# Quadcopter.net
KiCad netlist of a schematic drawn in EAGLE
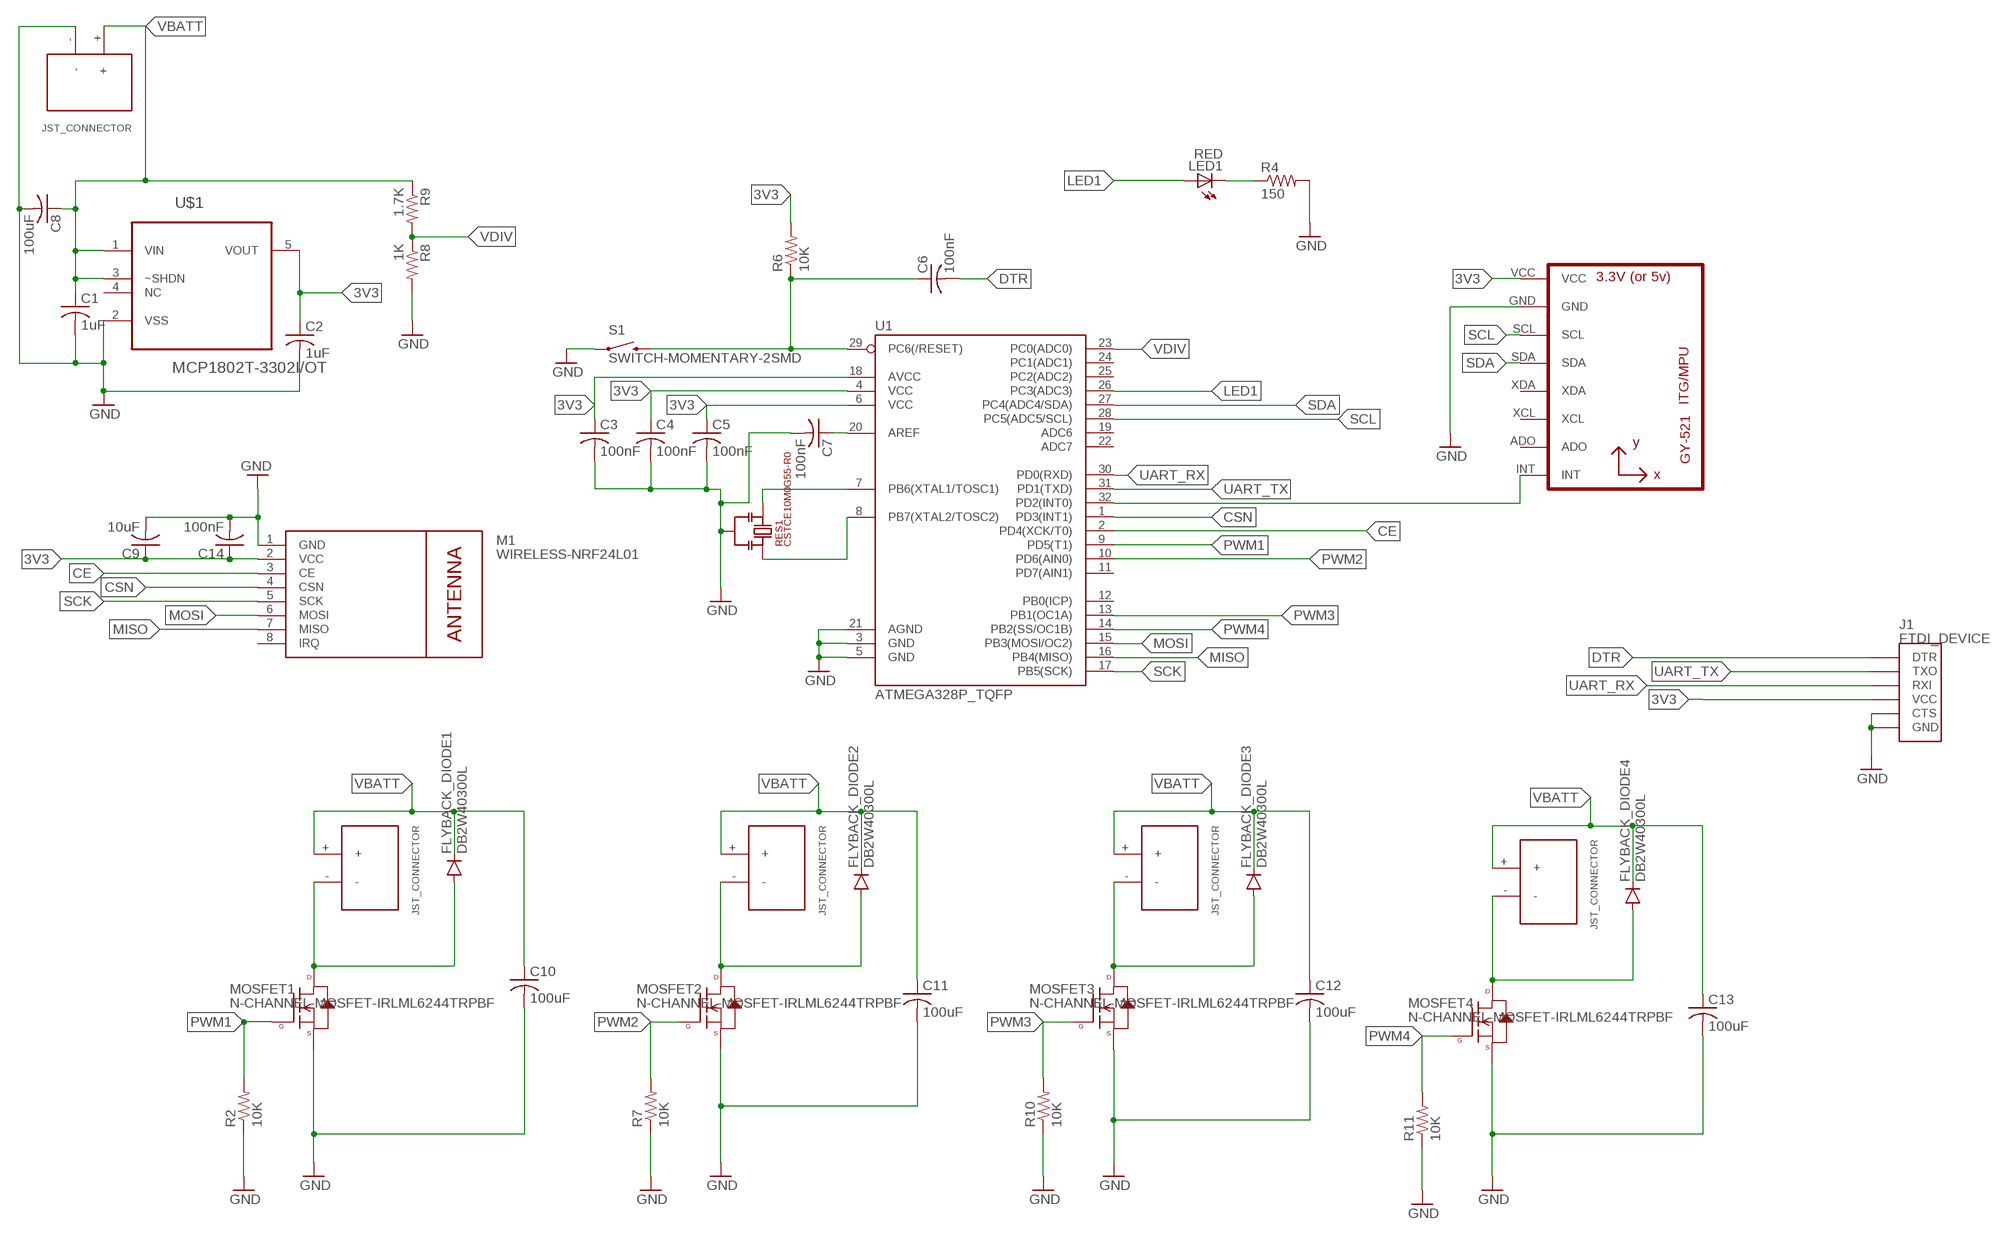
[diagram p0: schematic, sheet 1]

(export (version "E")
  (design (tool "Eeschema 10.0.6"))
  (components
    (comp (ref "C1")
      (value "1uF")
      (footprint "eagle-import:C0603")
      (libsource (lib "eagle-import") (part "C-USC0603"))
    )
    (comp (ref "C2")
      (value "1uF")
      (footprint "eagle-import:C0603")
      (libsource (lib "eagle-import") (part "C-USC0603"))
    )
    (comp (ref "C3")
      (value "100nF")
      (footprint "eagle-import:C0603")
      (libsource (lib "eagle-import") (part "C-USC0603"))
    )
    (comp (ref "C4")
      (value "100nF")
      (footprint "eagle-import:C0603")
      (libsource (lib "eagle-import") (part "C-USC0603"))
    )
    (comp (ref "C5")
      (value "100nF")
      (footprint "eagle-import:C0603")
      (libsource (lib "eagle-import") (part "C-USC0603"))
    )
    (comp (ref "C6")
      (value "100nF")
      (footprint "eagle-import:C0603")
      (libsource (lib "eagle-import") (part "C-USC0603"))
    )
    (comp (ref "C7")
      (value "100nF")
      (footprint "eagle-import:C0603")
      (libsource (lib "eagle-import") (part "C-USC0603"))
    )
    (comp (ref "C8")
      (value "100uF")
      (footprint "eagle-import:C1210")
      (libsource (lib "eagle-import") (part "C-USC1210"))
    )
    (comp (ref "C9")
      (value "10uF")
      (footprint "eagle-import:C0603")
      (libsource (lib "eagle-import") (part "C-USC0603"))
    )
    (comp (ref "C10")
      (value "100uF")
      (footprint "eagle-import:C1210")
      (libsource (lib "eagle-import") (part "C-USC1210"))
    )
    (comp (ref "C11")
      (value "100uF")
      (footprint "eagle-import:C1210")
      (libsource (lib "eagle-import") (part "C-USC1210"))
    )
    (comp (ref "C12")
      (value "100uF")
      (footprint "eagle-import:C1210")
      (libsource (lib "eagle-import") (part "C-USC1210"))
    )
    (comp (ref "C13")
      (value "100uF")
      (footprint "eagle-import:C1210")
      (libsource (lib "eagle-import") (part "C-USC1210"))
    )
    (comp (ref "C14")
      (value "100nF")
      (footprint "eagle-import:C0603")
      (libsource (lib "eagle-import") (part "C-USC0603"))
    )
    (comp (ref "FLYBACK_DIODE1")
      (value "DB2W40300L")
      (footprint "eagle-import:MINI2-F3-B")
      (libsource (lib "eagle-import") (part "DB2W40300L"))
    )
    (comp (ref "FLYBACK_DIODE2")
      (value "DB2W40300L")
      (footprint "eagle-import:MINI2-F3-B")
      (libsource (lib "eagle-import") (part "DB2W40300L"))
    )
    (comp (ref "FLYBACK_DIODE3")
      (value "DB2W40300L")
      (footprint "eagle-import:MINI2-F3-B")
      (libsource (lib "eagle-import") (part "DB2W40300L"))
    )
    (comp (ref "FLYBACK_DIODE4")
      (value "DB2W40300L")
      (footprint "eagle-import:MINI2-F3-B")
      (libsource (lib "eagle-import") (part "DB2W40300L"))
    )
    (comp (ref "J1")
      (value "FTDI_DEVICE")
      (footprint "eagle-import:FTDI_DEVICE_SIDE")
      (libsource (lib "eagle-import") (part "FTDI_DEVICE"))
    )
    (comp (ref "LED1")
      (value "RED")
      (footprint "eagle-import:CHIP-LED0603")
      (libsource (lib "eagle-import") (part "LEDCHIP-LED0603"))
    )
    (comp (ref "M1")
      (value "WIRELESS-NRF24L01")
      (footprint "eagle-import:WIRELESS-NRF24L01")
      (libsource (lib "eagle-import") (part "WIRELESS-NRF24L01"))
    )
    (comp (ref "MOSFET1")
      (value "N-CHANNEL-MOSFET-IRLML6244TRPBF")
      (footprint "eagle-import:SOT23-3")
      (libsource (lib "eagle-import") (part "N-CHANNEL-MOSFET-IRLML6244TRPBF"))
    )
    (comp (ref "MOSFET2")
      (value "N-CHANNEL-MOSFET-IRLML6244TRPBF")
      (footprint "eagle-import:SOT23-3")
      (libsource (lib "eagle-import") (part "N-CHANNEL-MOSFET-IRLML6244TRPBF"))
    )
    (comp (ref "MOSFET3")
      (value "N-CHANNEL-MOSFET-IRLML6244TRPBF")
      (footprint "eagle-import:SOT23-3")
      (libsource (lib "eagle-import") (part "N-CHANNEL-MOSFET-IRLML6244TRPBF"))
    )
    (comp (ref "MOSFET4")
      (value "N-CHANNEL-MOSFET-IRLML6244TRPBF")
      (footprint "eagle-import:SOT23-3")
      (libsource (lib "eagle-import") (part "N-CHANNEL-MOSFET-IRLML6244TRPBF"))
    )
    (comp (ref "MOTOR")
      (value "JST_CONNECTOR_FEMALE")
      (footprint "eagle-import:JST_CONNECTOR_FEMALE")
      (libsource (lib "eagle-import") (part "JST_CONNECTOR_FEMALE"))
    )
    (comp (ref "MOTOR1")
      (value "JST_CONNECTOR_FEMALE")
      (footprint "eagle-import:JST_CONNECTOR_FEMALE")
      (libsource (lib "eagle-import") (part "JST_CONNECTOR_FEMALE"))
    )
    (comp (ref "MOTOR2")
      (value "JST_CONNECTOR_FEMALE")
      (footprint "eagle-import:JST_CONNECTOR_FEMALE")
      (libsource (lib "eagle-import") (part "JST_CONNECTOR_FEMALE"))
    )
    (comp (ref "MOTOR3")
      (value "JST_CONNECTOR_FEMALE")
      (footprint "eagle-import:JST_CONNECTOR_FEMALE")
      (libsource (lib "eagle-import") (part "JST_CONNECTOR_FEMALE"))
    )
    (comp (ref "R2")
      (value "10K")
      (footprint "eagle-import:R0603")
      (libsource (lib "eagle-import") (part "R-US_R0603"))
    )
    (comp (ref "R4")
      (value "150")
      (footprint "eagle-import:R0603")
      (libsource (lib "eagle-import") (part "R-US_R0603"))
    )
    (comp (ref "R6")
      (value "10K")
      (footprint "eagle-import:R0603")
      (libsource (lib "eagle-import") (part "R-US_R0603"))
    )
    (comp (ref "R7")
      (value "10K")
      (footprint "eagle-import:R0603")
      (libsource (lib "eagle-import") (part "R-US_R0603"))
    )
    (comp (ref "R8")
      (value "1K")
      (footprint "eagle-import:R0603")
      (libsource (lib "eagle-import") (part "R-US_R0603"))
    )
    (comp (ref "R9")
      (value "1.7K")
      (footprint "eagle-import:R0603")
      (libsource (lib "eagle-import") (part "R-US_R0603"))
    )
    (comp (ref "R10")
      (value "10K")
      (footprint "eagle-import:R0603")
      (libsource (lib "eagle-import") (part "R-US_R0603"))
    )
    (comp (ref "R11")
      (value "10K")
      (footprint "eagle-import:R0603")
      (libsource (lib "eagle-import") (part "R-US_R0603"))
    )
    (comp (ref "RES1")
      (value "CSTCE10M0G55-R0")
      (footprint "eagle-import:CSTCE16M0V53-R0")
      (libsource (lib "eagle-import") (part "CSTCE-RESONATOR"))
    )
    (comp (ref "S1")
      (value "SWITCH-MOMENTARY-2SMD")
      (footprint "eagle-import:TACTILE-SWITCH-SMD")
      (libsource (lib "eagle-import") (part "SWITCH-MOMENTARY-2SMD"))
    )
    (comp (ref "U$1")
      (value "MCP1802T-3302I/OT")
      (footprint "eagle-import:SOT95P270X145-5N")
      (fields (field (name "MPN") "MCP1802T-3002I/OT"))
      (libsource (lib "eagle-import") (part "MCP1802T-3002I/OT"))
    )
    (comp (ref "U$2")
      (value "JST_Battery")
      (footprint "eagle-import:JST_CONNECTOR_FEMALE")
      (libsource (lib "eagle-import") (part "JST_CONNECTOR_FEMALE"))
    )
    (comp (ref "U1")
      (value "ATMEGA328P_TQFP")
      (footprint "eagle-import:TQFP32-08")
      (libsource (lib "eagle-import") (part "ATMEGA328P_TQFP"))
    )
    (comp (ref "U3")
      (value "GY-521MPU6050")
      (footprint "eagle-import:GY-521")
      (libsource (lib "eagle-import") (part "GY-521MPU6050"))
    )
  )
  (nets
    (net (code "1") (name "3V3") (class "Default")
      (node (ref "C14") (pin "1") (pinfunction "1_1") (pintype "passive"))
      (node (ref "C2") (pin "1") (pinfunction "1_1") (pintype "passive"))
      (node (ref "C3") (pin "1") (pinfunction "1_1") (pintype "passive"))
      (node (ref "C4") (pin "1") (pinfunction "1_1") (pintype "passive"))
      (node (ref "C5") (pin "1") (pinfunction "1_1") (pintype "passive"))
      (node (ref "C9") (pin "1") (pinfunction "1_1") (pintype "passive"))
      (node (ref "J1") (pin "P$4") (pinfunction "VCC_P$4") (pintype "bidirectional"))
      (node (ref "M1") (pin "2") (pinfunction "VCC_2") (pintype "power_in"))
      (node (ref "R6") (pin "2") (pinfunction "2_2") (pintype "passive"))
      (node (ref "U$1") (pin "5") (pinfunction "VOUT_5") (pintype "output"))
      (node (ref "U1") (pin "18") (pinfunction "AVCC_18") (pintype "bidirectional"))
      (node (ref "U1") (pin "4") (pinfunction "VCC_4") (pintype "bidirectional"))
      (node (ref "U1") (pin "6") (pinfunction "VCC_6") (pintype "bidirectional"))
      (node (ref "U3") (pin "VCC") (pinfunction "VCC_VCC") (pintype "bidirectional"))
    )
    (net (code "2") (name "CE") (class "Default")
      (node (ref "M1") (pin "3") (pinfunction "CE_3") (pintype "bidirectional"))
      (node (ref "U1") (pin "2") (pinfunction "PD4(XCK/T0)_2") (pintype "bidirectional"))
    )
    (net (code "3") (name "CSN") (class "Default")
      (node (ref "M1") (pin "4") (pinfunction "CSN_4") (pintype "bidirectional"))
      (node (ref "U1") (pin "1") (pinfunction "PD3(INT1)_1") (pintype "bidirectional"))
    )
    (net (code "4") (name "DTR") (class "Default")
      (node (ref "C6") (pin "2") (pinfunction "2_2") (pintype "passive"))
      (node (ref "J1") (pin "P$1") (pinfunction "DTR_P$1") (pintype "bidirectional"))
    )
    (net (code "5") (name "GND") (class "Default")
      (node (ref "C1") (pin "2") (pinfunction "2_2") (pintype "passive"))
      (node (ref "C10") (pin "2") (pinfunction "2_2") (pintype "passive"))
      (node (ref "C11") (pin "2") (pinfunction "2_2") (pintype "passive"))
      (node (ref "C12") (pin "2") (pinfunction "2_2") (pintype "passive"))
      (node (ref "C13") (pin "2") (pinfunction "2_2") (pintype "passive"))
      (node (ref "C14") (pin "2") (pinfunction "2_2") (pintype "passive"))
      (node (ref "C2") (pin "2") (pinfunction "2_2") (pintype "passive"))
      (node (ref "C3") (pin "2") (pinfunction "2_2") (pintype "passive"))
      (node (ref "C4") (pin "2") (pinfunction "2_2") (pintype "passive"))
      (node (ref "C5") (pin "2") (pinfunction "2_2") (pintype "passive"))
      (node (ref "C7") (pin "2") (pinfunction "2_2") (pintype "passive"))
      (node (ref "C8") (pin "2") (pinfunction "2_2") (pintype "passive"))
      (node (ref "C9") (pin "2") (pinfunction "2_2") (pintype "passive"))
      (node (ref "J1") (pin "P$5") (pinfunction "CTS_P$5") (pintype "bidirectional"))
      (node (ref "J1") (pin "P$6") (pinfunction "GND_P$6") (pintype "bidirectional"))
      (node (ref "M1") (pin "1") (pinfunction "GND_1") (pintype "power_in"))
      (node (ref "MOSFET1") (pin "2") (pinfunction "S_2") (pintype "passive"))
      (node (ref "MOSFET2") (pin "2") (pinfunction "S_2") (pintype "passive"))
      (node (ref "MOSFET3") (pin "2") (pinfunction "S_2") (pintype "passive"))
      (node (ref "MOSFET4") (pin "2") (pinfunction "S_2") (pintype "passive"))
      (node (ref "R10") (pin "1") (pinfunction "1_1") (pintype "passive"))
      (node (ref "R11") (pin "1") (pinfunction "1_1") (pintype "passive"))
      (node (ref "R2") (pin "1") (pinfunction "1_1") (pintype "passive"))
      (node (ref "R4") (pin "2") (pinfunction "2_2") (pintype "passive"))
      (node (ref "R7") (pin "1") (pinfunction "1_1") (pintype "passive"))
      (node (ref "R8") (pin "2") (pinfunction "2_2") (pintype "passive"))
      (node (ref "RES1") (pin "P$2") (pinfunction "P$2_P$2") (pintype "bidirectional"))
      (node (ref "S1") (pin "1") (pinfunction "1_1") (pintype "passive"))
      (node (ref "U$1") (pin "2") (pinfunction "VSS_2") (pintype "passive"))
      (node (ref "U$2") (pin "-") (pinfunction "-_-") (pintype "bidirectional"))
      (node (ref "U1") (pin "21") (pinfunction "AGND_21") (pintype "bidirectional"))
      (node (ref "U1") (pin "3") (pinfunction "GND_3") (pintype "bidirectional"))
      (node (ref "U1") (pin "5") (pinfunction "GND_5") (pintype "bidirectional"))
      (node (ref "U3") (pin "GND") (pinfunction "GND_GND") (pintype "bidirectional"))
    )
    (net (code "6") (name "LED1") (class "Default")
      (node (ref "LED1") (pin "A") (pinfunction "A_A") (pintype "passive"))
      (node (ref "U1") (pin "26") (pinfunction "PC3(ADC3)_26") (pintype "bidirectional"))
    )
    (net (code "7") (name "MISO") (class "Default")
      (node (ref "M1") (pin "7") (pinfunction "MISO_7") (pintype "bidirectional"))
      (node (ref "U1") (pin "16") (pinfunction "PB4(MISO)_16") (pintype "bidirectional"))
    )
    (net (code "8") (name "MOSI") (class "Default")
      (node (ref "M1") (pin "6") (pinfunction "MOSI_6") (pintype "bidirectional"))
      (node (ref "U1") (pin "15") (pinfunction "PB3(MOSI/OC2)_15") (pintype "bidirectional"))
    )
    (net (code "9") (name "Net-(FLYBACK_DIODE1-PPIN)") (class "Default")
      (node (ref "FLYBACK_DIODE1") (pin "POS") (pinfunction "PPIN_POS") (pintype "passive"))
      (node (ref "MOSFET1") (pin "3") (pinfunction "D_3") (pintype "passive"))
      (node (ref "MOTOR") (pin "-") (pinfunction "-_-") (pintype "bidirectional"))
    )
    (net (code "10") (name "Net-(FLYBACK_DIODE2-PPIN)") (class "Default")
      (node (ref "FLYBACK_DIODE2") (pin "POS") (pinfunction "PPIN_POS") (pintype "passive"))
      (node (ref "MOSFET2") (pin "3") (pinfunction "D_3") (pintype "passive"))
      (node (ref "MOTOR1") (pin "-") (pinfunction "-_-") (pintype "bidirectional"))
    )
    (net (code "11") (name "Net-(FLYBACK_DIODE3-PPIN)") (class "Default")
      (node (ref "FLYBACK_DIODE3") (pin "POS") (pinfunction "PPIN_POS") (pintype "passive"))
      (node (ref "MOSFET3") (pin "3") (pinfunction "D_3") (pintype "passive"))
      (node (ref "MOTOR2") (pin "-") (pinfunction "-_-") (pintype "bidirectional"))
    )
    (net (code "12") (name "Net-(FLYBACK_DIODE4-PPIN)") (class "Default")
      (node (ref "FLYBACK_DIODE4") (pin "POS") (pinfunction "PPIN_POS") (pintype "passive"))
      (node (ref "MOSFET4") (pin "3") (pinfunction "D_3") (pintype "passive"))
      (node (ref "MOTOR3") (pin "-") (pinfunction "-_-") (pintype "bidirectional"))
    )
    (net (code "13") (name "Net-(LED1-PadC)") (class "Default")
      (node (ref "LED1") (pin "C") (pinfunction "C_C") (pintype "passive"))
      (node (ref "R4") (pin "1") (pinfunction "1_1") (pintype "passive"))
    )
    (net (code "14") (name "Net-(S1-2)") (class "Default")
      (node (ref "C6") (pin "1") (pinfunction "1_1") (pintype "passive"))
      (node (ref "R6") (pin "1") (pinfunction "1_1") (pintype "passive"))
      (node (ref "S1") (pin "3") (pinfunction "2_3") (pintype "passive"))
      (node (ref "U1") (pin "29") (pinfunction "PC6(/RESET)_29") (pintype "bidirectional"))
    )
    (net (code "15") (name "Net-(U1-AREF)") (class "Default")
      (node (ref "C7") (pin "1") (pinfunction "1_1") (pintype "passive"))
      (node (ref "U1") (pin "20") (pinfunction "AREF_20") (pintype "bidirectional"))
    )
    (net (code "16") (name "Net-(U1-PB6(XTAL1{slash}TOSC1))") (class "Default")
      (node (ref "RES1") (pin "P$3") (pinfunction "P$3_P$3") (pintype "bidirectional"))
      (node (ref "U1") (pin "7") (pinfunction "PB6(XTAL1/TOSC1)_7") (pintype "bidirectional"))
    )
    (net (code "17") (name "Net-(U1-PB7(XTAL2{slash}TOSC2))") (class "Default")
      (node (ref "RES1") (pin "P$1") (pinfunction "P$1_P$1") (pintype "bidirectional"))
      (node (ref "U1") (pin "8") (pinfunction "PB7(XTAL2/TOSC2)_8") (pintype "bidirectional"))
    )
    (net (code "18") (name "Net-(U1-PD2(INT0))") (class "Default")
      (node (ref "U1") (pin "32") (pinfunction "PD2(INT0)_32") (pintype "bidirectional"))
      (node (ref "U3") (pin "INT") (pinfunction "INT_INT") (pintype "bidirectional"))
    )
    (net (code "19") (name "PWM1") (class "Default")
      (node (ref "MOSFET1") (pin "1") (pinfunction "G_1") (pintype "passive"))
      (node (ref "R2") (pin "2") (pinfunction "2_2") (pintype "passive"))
      (node (ref "U1") (pin "9") (pinfunction "PD5(T1)_9") (pintype "bidirectional"))
    )
    (net (code "20") (name "PWM2") (class "Default")
      (node (ref "MOSFET2") (pin "1") (pinfunction "G_1") (pintype "passive"))
      (node (ref "R7") (pin "2") (pinfunction "2_2") (pintype "passive"))
      (node (ref "U1") (pin "10") (pinfunction "PD6(AIN0)_10") (pintype "bidirectional"))
    )
    (net (code "21") (name "PWM3") (class "Default")
      (node (ref "MOSFET3") (pin "1") (pinfunction "G_1") (pintype "passive"))
      (node (ref "R10") (pin "2") (pinfunction "2_2") (pintype "passive"))
      (node (ref "U1") (pin "13") (pinfunction "PB1(OC1A)_13") (pintype "bidirectional"))
    )
    (net (code "22") (name "PWM4") (class "Default")
      (node (ref "MOSFET4") (pin "1") (pinfunction "G_1") (pintype "passive"))
      (node (ref "R11") (pin "2") (pinfunction "2_2") (pintype "passive"))
      (node (ref "U1") (pin "14") (pinfunction "PB2(SS/OC1B)_14") (pintype "bidirectional"))
    )
    (net (code "23") (name "SCK") (class "Default")
      (node (ref "M1") (pin "5") (pinfunction "SCK_5") (pintype "bidirectional"))
      (node (ref "U1") (pin "17") (pinfunction "PB5(SCK)_17") (pintype "bidirectional"))
    )
    (net (code "24") (name "SCL") (class "Default")
      (node (ref "U1") (pin "28") (pinfunction "PC5(ADC5/SCL)_28") (pintype "bidirectional"))
      (node (ref "U3") (pin "SCL") (pinfunction "SCL_SCL") (pintype "bidirectional"))
    )
    (net (code "25") (name "SDA") (class "Default")
      (node (ref "U1") (pin "27") (pinfunction "PC4(ADC4/SDA)_27") (pintype "bidirectional"))
      (node (ref "U3") (pin "SDA") (pinfunction "SDA_SDA") (pintype "bidirectional"))
    )
    (net (code "26") (name "UART_RX") (class "Default")
      (node (ref "J1") (pin "P$3") (pinfunction "RXI_P$3") (pintype "bidirectional"))
      (node (ref "U1") (pin "30") (pinfunction "PD0(RXD)_30") (pintype "bidirectional"))
    )
    (net (code "27") (name "UART_TX") (class "Default")
      (node (ref "J1") (pin "P$2") (pinfunction "TXO_P$2") (pintype "bidirectional"))
      (node (ref "U1") (pin "31") (pinfunction "PD1(TXD)_31") (pintype "bidirectional"))
    )
    (net (code "28") (name "VBATT") (class "Default")
      (node (ref "C1") (pin "1") (pinfunction "1_1") (pintype "passive"))
      (node (ref "C10") (pin "1") (pinfunction "1_1") (pintype "passive"))
      (node (ref "C11") (pin "1") (pinfunction "1_1") (pintype "passive"))
      (node (ref "C12") (pin "1") (pinfunction "1_1") (pintype "passive"))
      (node (ref "C13") (pin "1") (pinfunction "1_1") (pintype "passive"))
      (node (ref "C8") (pin "1") (pinfunction "1_1") (pintype "passive"))
      (node (ref "FLYBACK_DIODE1") (pin "NEG") (pinfunction "GPIN_NEG") (pintype "passive"))
      (node (ref "FLYBACK_DIODE2") (pin "NEG") (pinfunction "GPIN_NEG") (pintype "passive"))
      (node (ref "FLYBACK_DIODE3") (pin "NEG") (pinfunction "GPIN_NEG") (pintype "passive"))
      (node (ref "FLYBACK_DIODE4") (pin "NEG") (pinfunction "GPIN_NEG") (pintype "passive"))
      (node (ref "MOTOR") (pin "+") (pinfunction "+_+") (pintype "bidirectional"))
      (node (ref "MOTOR1") (pin "+") (pinfunction "+_+") (pintype "bidirectional"))
      (node (ref "MOTOR2") (pin "+") (pinfunction "+_+") (pintype "bidirectional"))
      (node (ref "MOTOR3") (pin "+") (pinfunction "+_+") (pintype "bidirectional"))
      (node (ref "R9") (pin "1") (pinfunction "1_1") (pintype "passive"))
      (node (ref "U$1") (pin "1") (pinfunction "VIN_1") (pintype "power_in"))
      (node (ref "U$1") (pin "3") (pinfunction "~{SHDN}_3") (pintype "input"))
      (node (ref "U$2") (pin "+") (pinfunction "+_+") (pintype "bidirectional"))
    )
    (net (code "29") (name "VDIV") (class "Default")
      (node (ref "R8") (pin "1") (pinfunction "1_1") (pintype "passive"))
      (node (ref "R9") (pin "2") (pinfunction "2_2") (pintype "passive"))
      (node (ref "U1") (pin "23") (pinfunction "PC0(ADC0)_23") (pintype "bidirectional"))
    )
    (net (code "30") (name "unconnected-(M1-IRQ-Pad8)") (class "Default")
      (node (ref "M1") (pin "8") (pinfunction "IRQ_8") (pintype "bidirectional"))
    )
    (net (code "31") (name "unconnected-(U$1-NC-Pad4)") (class "Default")
      (node (ref "U$1") (pin "4") (pinfunction "NC_4") (pintype "no_connect"))
    )
    (net (code "32") (name "unconnected-(U1-ADC6-Pad19)") (class "Default")
      (node (ref "U1") (pin "19") (pinfunction "ADC6_19") (pintype "bidirectional"))
    )
    (net (code "33") (name "unconnected-(U1-ADC7-Pad22)") (class "Default")
      (node (ref "U1") (pin "22") (pinfunction "ADC7_22") (pintype "bidirectional"))
    )
    (net (code "34") (name "unconnected-(U1-PB0(ICP)-Pad12)") (class "Default")
      (node (ref "U1") (pin "12") (pinfunction "PB0(ICP)_12") (pintype "bidirectional"))
    )
    (net (code "35") (name "unconnected-(U1-PC1(ADC1)-Pad24)") (class "Default")
      (node (ref "U1") (pin "24") (pinfunction "PC1(ADC1)_24") (pintype "bidirectional"))
    )
    (net (code "36") (name "unconnected-(U1-PC2(ADC2)-Pad25)") (class "Default")
      (node (ref "U1") (pin "25") (pinfunction "PC2(ADC2)_25") (pintype "bidirectional"))
    )
    (net (code "37") (name "unconnected-(U1-PD7(AIN1)-Pad11)") (class "Default")
      (node (ref "U1") (pin "11") (pinfunction "PD7(AIN1)_11") (pintype "bidirectional"))
    )
    (net (code "38") (name "unconnected-(U3-PadADO)") (class "Default")
      (node (ref "U3") (pin "ADO") (pinfunction "ADO_ADO") (pintype "bidirectional"))
    )
    (net (code "39") (name "unconnected-(U3-PadXCL)") (class "Default")
      (node (ref "U3") (pin "XCL") (pinfunction "XCL_XCL") (pintype "bidirectional"))
    )
    (net (code "40") (name "unconnected-(U3-PadXDA)") (class "Default")
      (node (ref "U3") (pin "XDA") (pinfunction "XDA_XDA") (pintype "bidirectional"))
    )
  )
)
